# blink1mk3_micro1d2.net
KiCad netlist of a schematic drawn in EAGLE
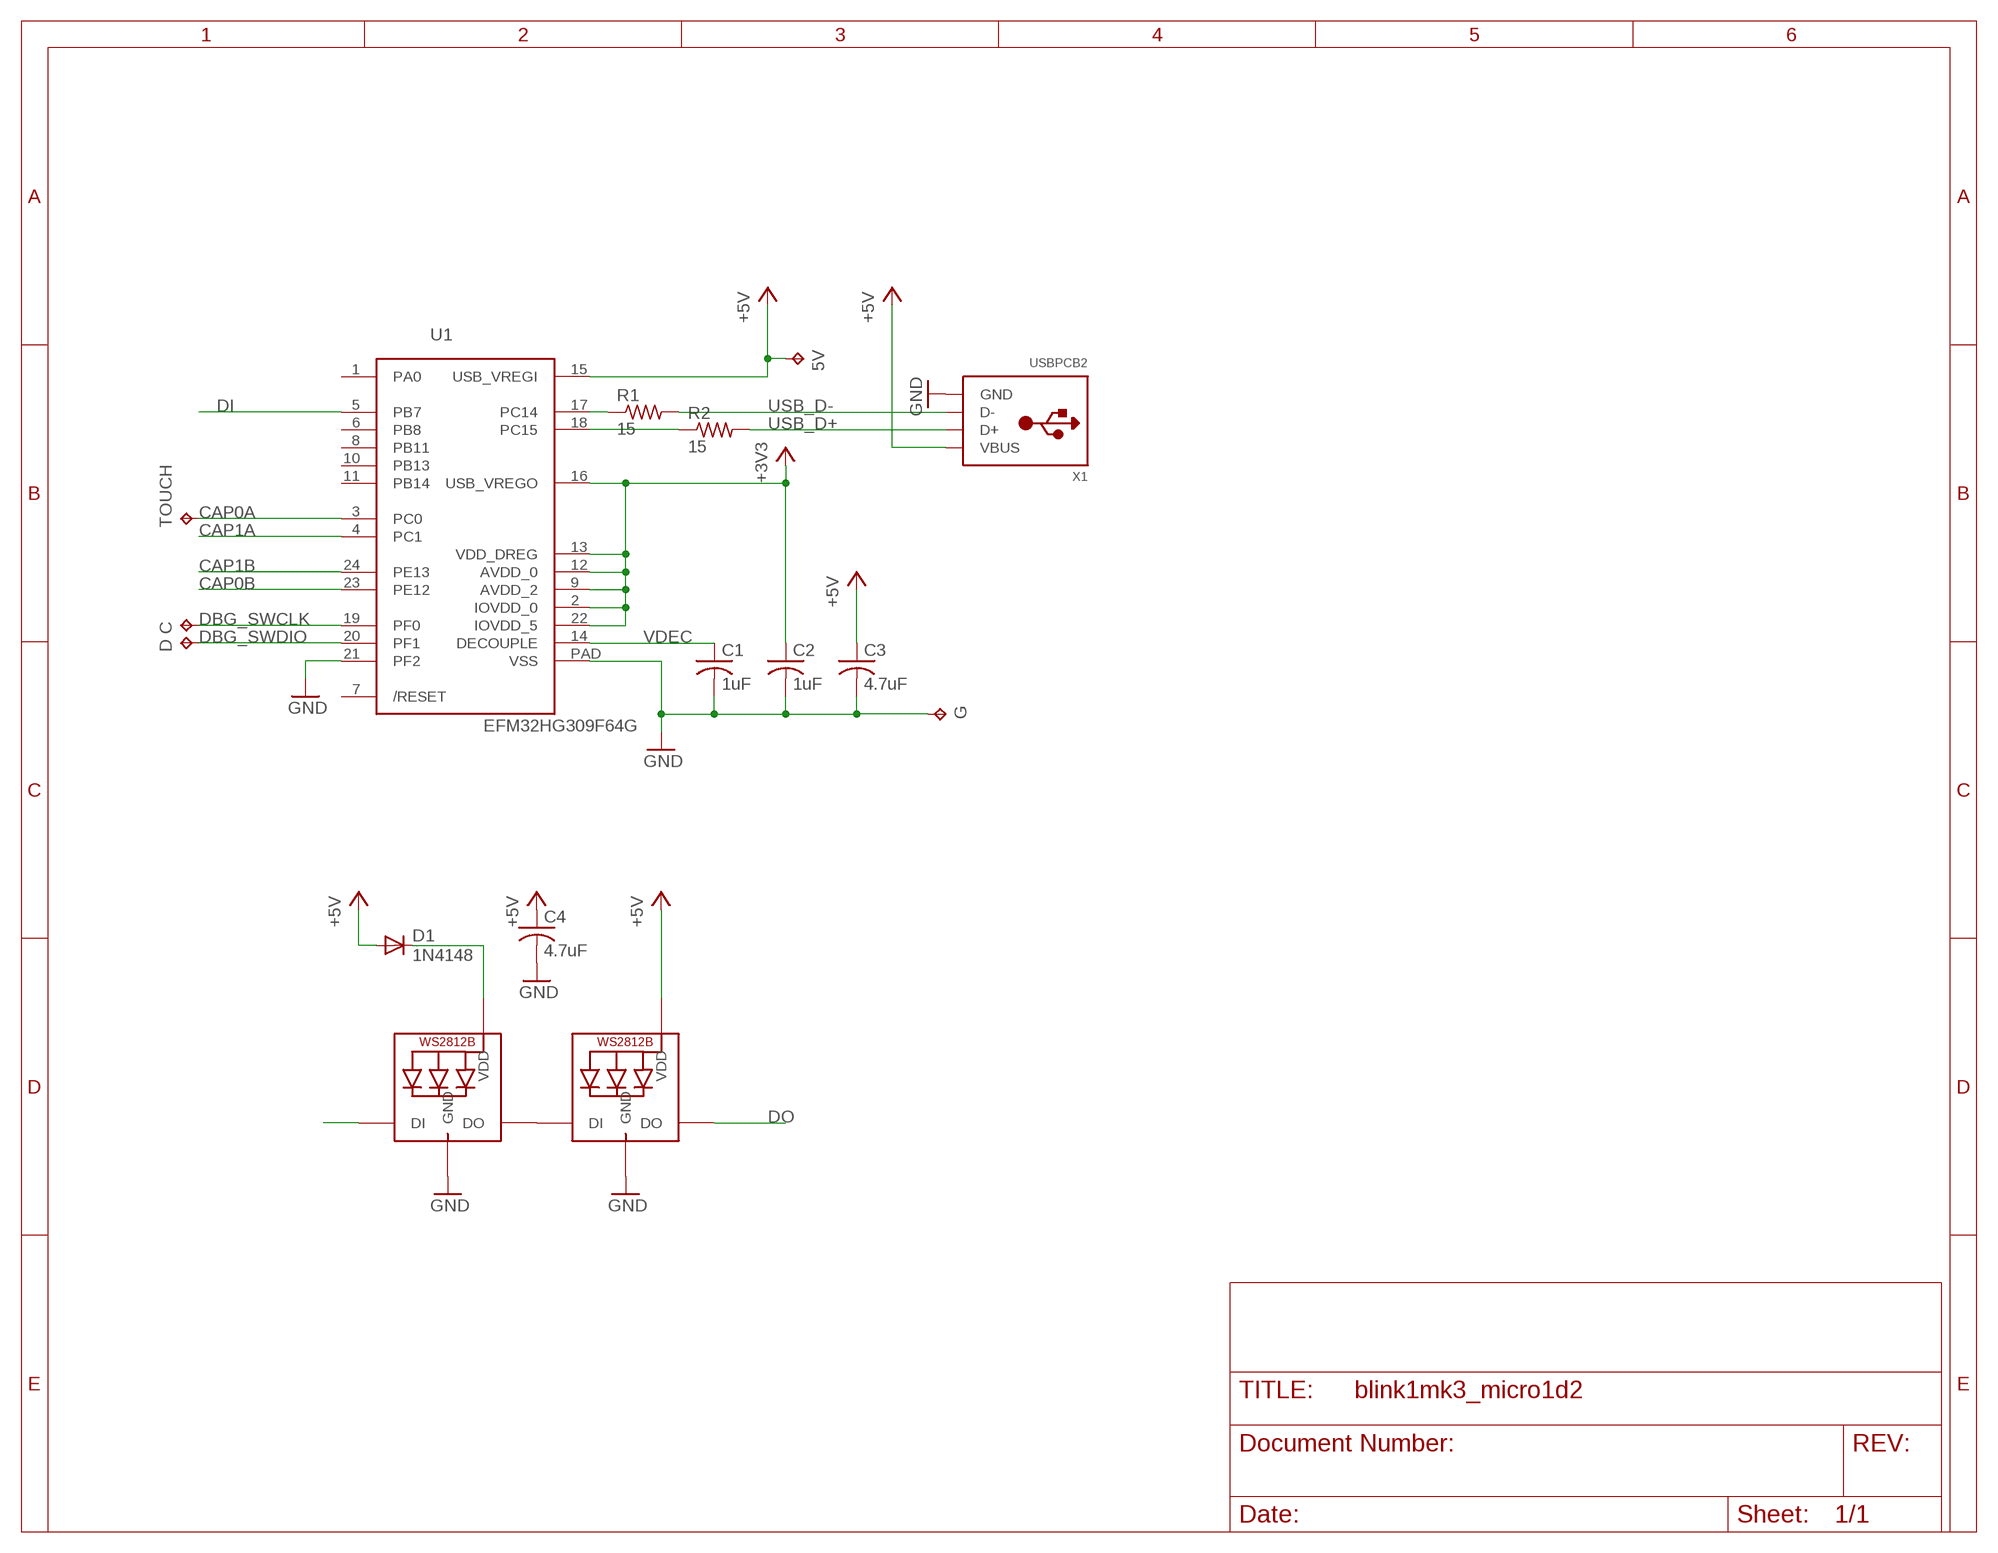
[diagram p0: schematic, sheet 1]

(export (version "E")
  (design (tool "Eeschema 10.0.6"))
  (components
    (comp (ref "5V")
      (value "TPTP10R")
      (footprint "eagle-import:TP10R")
      (libsource (lib "eagle-import") (part "TPTP10R"))
    )
    (comp (ref "C")
      (value "TPTP10R")
      (footprint "eagle-import:TP10R")
      (libsource (lib "eagle-import") (part "TPTP10R"))
    )
    (comp (ref "C1")
      (value "1uF")
      (footprint "eagle-import:C0402")
      (libsource (lib "eagle-import") (part "C-USC0402"))
    )
    (comp (ref "C2")
      (value "1uF")
      (footprint "eagle-import:C0402")
      (libsource (lib "eagle-import") (part "C-USC0402"))
    )
    (comp (ref "C3")
      (value "4.7uF")
      (footprint "eagle-import:C0402")
      (libsource (lib "eagle-import") (part "C-USC0402"))
    )
    (comp (ref "C4")
      (value "4.7uF")
      (footprint "eagle-import:C0402")
      (libsource (lib "eagle-import") (part "C-USC0402"))
    )
    (comp (ref "D")
      (value "TPTP10R")
      (footprint "eagle-import:TP10R")
      (libsource (lib "eagle-import") (part "TPTP10R"))
    )
    (comp (ref "D1")
      (value "1N4148")
      (footprint "eagle-import:SOD523")
      (libsource (lib "eagle-import") (part "DIODE-SOD523"))
    )
    (comp (ref "G")
      (value "TPTP10SQ")
      (footprint "eagle-import:TP10SQ")
      (libsource (lib "eagle-import") (part "TPTP10SQ"))
    )
    (comp (ref "LED1")
      (value "WS2812B4020SIDE")
      (footprint "eagle-import:SK6812-SIDE")
      (libsource (lib "eagle-import") (part "WS2812B4020SIDE"))
    )
    (comp (ref "LED2")
      (value "WS2812B4020SIDE")
      (footprint "eagle-import:SK6812-SIDE")
      (libsource (lib "eagle-import") (part "WS2812B4020SIDE"))
    )
    (comp (ref "R1")
      (value "15")
      (footprint "eagle-import:R0402")
      (libsource (lib "eagle-import") (part "R-US_R0402"))
    )
    (comp (ref "R2")
      (value "15")
      (footprint "eagle-import:R0402")
      (libsource (lib "eagle-import") (part "R-US_R0402"))
    )
    (comp (ref "TOUCH")
      (value "TPTP10R")
      (footprint "eagle-import:TP10R")
      (libsource (lib "eagle-import") (part "TPTP10R"))
    )
    (comp (ref "U1")
      (value "EFM32HG309F64G")
      (footprint "eagle-import:QFN24PAD")
      (libsource (lib "eagle-import") (part "EFM32HG309F64G"))
    )
    (comp (ref "X1")
      (value "USBPCB2")
      (footprint "eagle-import:USB-A-PCB-2")
      (libsource (lib "eagle-import") (part "USBPCB2"))
    )
  )
  (nets
    (net (code "1") (name "+3V3") (class "Default")
      (node (ref "C2") (pin "1") (pinfunction "1_1") (pintype "passive"))
      (node (ref "U1") (pin "12") (pinfunction "AVDD_0_12") (pintype "bidirectional"))
      (node (ref "U1") (pin "13") (pinfunction "VDD_DREG_13") (pintype "bidirectional"))
      (node (ref "U1") (pin "16") (pinfunction "USB_VREGO_16") (pintype "bidirectional"))
      (node (ref "U1") (pin "2") (pinfunction "IOVDD_0_2") (pintype "bidirectional"))
      (node (ref "U1") (pin "22") (pinfunction "IOVDD_5_22") (pintype "bidirectional"))
      (node (ref "U1") (pin "9") (pinfunction "AVDD_2_9") (pintype "bidirectional"))
    )
    (net (code "2") (name "+5V") (class "Default")
      (node (ref "5V") (pin "TP") (pinfunction "TP_TP") (pintype "input"))
      (node (ref "C3") (pin "1") (pinfunction "1_1") (pintype "passive"))
      (node (ref "C4") (pin "1") (pinfunction "1_1") (pintype "passive"))
      (node (ref "D1") (pin "A") (pinfunction "A_A") (pintype "passive"))
      (node (ref "LED2") (pin "1-VDD") (pinfunction "VDD_1-VDD") (pintype "power_in"))
      (node (ref "U1") (pin "15") (pinfunction "USB_VREGI_15") (pintype "bidirectional"))
      (node (ref "X1") (pin "5V") (pinfunction "VBUS_5V") (pintype "power_in"))
    )
    (net (code "3") (name "/CAP0A") (class "Default")
      (node (ref "TOUCH") (pin "TP") (pinfunction "TP_TP") (pintype "input"))
      (node (ref "U1") (pin "3") (pinfunction "PC0_3") (pintype "bidirectional"))
    )
    (net (code "4") (name "/CAP0B") (class "Default")
      (node (ref "U1") (pin "23") (pinfunction "PE12_23") (pintype "bidirectional"))
    )
    (net (code "5") (name "/CAP1A") (class "Default")
      (node (ref "U1") (pin "4") (pinfunction "PC1_4") (pintype "bidirectional"))
    )
    (net (code "6") (name "/CAP1B") (class "Default")
      (node (ref "U1") (pin "24") (pinfunction "PE13_24") (pintype "bidirectional"))
    )
    (net (code "7") (name "/DBG_SWCLK") (class "Default")
      (node (ref "C") (pin "TP") (pinfunction "TP_TP") (pintype "input"))
      (node (ref "U1") (pin "19") (pinfunction "PF0_19") (pintype "bidirectional"))
    )
    (net (code "8") (name "/DBG_SWDIO") (class "Default")
      (node (ref "D") (pin "TP") (pinfunction "TP_TP") (pintype "input"))
      (node (ref "U1") (pin "20") (pinfunction "PF1_20") (pintype "bidirectional"))
    )
    (net (code "9") (name "/DI") (class "Default")
      (node (ref "LED1") (pin "4-DIN") (pinfunction "DI_4-DIN") (pintype "input"))
      (node (ref "U1") (pin "5") (pinfunction "PB7_5") (pintype "bidirectional"))
    )
    (net (code "10") (name "/DO") (class "Default")
      (node (ref "LED2") (pin "2-DOUT") (pinfunction "DO_2-DOUT") (pintype "output"))
    )
    (net (code "11") (name "/USB_D+") (class "Default")
      (node (ref "R2") (pin "2") (pinfunction "2_2") (pintype "passive"))
      (node (ref "X1") (pin "USB_P") (pinfunction "D+_USB_P") (pintype "bidirectional"))
    )
    (net (code "12") (name "/USB_D-") (class "Default")
      (node (ref "R1") (pin "2") (pinfunction "2_2") (pintype "passive"))
      (node (ref "X1") (pin "USB_M") (pinfunction "D-_USB_M") (pintype "bidirectional"))
    )
    (net (code "13") (name "/VDEC") (class "Default")
      (node (ref "C1") (pin "1") (pinfunction "1_1") (pintype "passive"))
      (node (ref "U1") (pin "14") (pinfunction "DECOUPLE_14") (pintype "bidirectional"))
    )
    (net (code "14") (name "GND") (class "Default")
      (node (ref "C1") (pin "2") (pinfunction "2_2") (pintype "passive"))
      (node (ref "C2") (pin "2") (pinfunction "2_2") (pintype "passive"))
      (node (ref "C3") (pin "2") (pinfunction "2_2") (pintype "passive"))
      (node (ref "C4") (pin "2") (pinfunction "2_2") (pintype "passive"))
      (node (ref "G") (pin "TP") (pinfunction "TP_TP") (pintype "input"))
      (node (ref "LED1") (pin "3-GND") (pinfunction "GND_3-GND") (pintype "power_in"))
      (node (ref "LED2") (pin "3-GND") (pinfunction "GND_3-GND") (pintype "power_in"))
      (node (ref "U1") (pin "21") (pinfunction "PF2_21") (pintype "bidirectional"))
      (node (ref "U1") (pin "PAD") (pinfunction "VSS_PAD") (pintype "bidirectional"))
      (node (ref "X1") (pin "GND") (pinfunction "GND_GND") (pintype "power_in"))
    )
    (net (code "15") (name "Net-(LED1-DO)") (class "Default")
      (node (ref "LED1") (pin "2-DOUT") (pinfunction "DO_2-DOUT") (pintype "output"))
      (node (ref "LED2") (pin "4-DIN") (pinfunction "DI_4-DIN") (pintype "input"))
    )
    (net (code "16") (name "Net-(LED1-VDD)") (class "Default")
      (node (ref "D1") (pin "C") (pinfunction "C_C") (pintype "passive"))
      (node (ref "LED1") (pin "1-VDD") (pinfunction "VDD_1-VDD") (pintype "power_in"))
    )
    (net (code "17") (name "Net-(U1-PC14)") (class "Default")
      (node (ref "R1") (pin "1") (pinfunction "1_1") (pintype "passive"))
      (node (ref "U1") (pin "17") (pinfunction "PC14_17") (pintype "bidirectional"))
    )
    (net (code "18") (name "Net-(U1-PC15)") (class "Default")
      (node (ref "R2") (pin "1") (pinfunction "1_1") (pintype "passive"))
      (node (ref "U1") (pin "18") (pinfunction "PC15_18") (pintype "bidirectional"))
    )
    (net (code "19") (name "unconnected-(U1-PA0-Pad1)") (class "Default")
      (node (ref "U1") (pin "1") (pinfunction "PA0_1") (pintype "bidirectional"))
    )
    (net (code "20") (name "unconnected-(U1-PB8-Pad6)") (class "Default")
      (node (ref "U1") (pin "6") (pinfunction "PB8_6") (pintype "bidirectional"))
    )
    (net (code "21") (name "unconnected-(U1-PB11-Pad8)") (class "Default")
      (node (ref "U1") (pin "8") (pinfunction "PB11_8") (pintype "bidirectional"))
    )
    (net (code "22") (name "unconnected-(U1-PB13-Pad10)") (class "Default")
      (node (ref "U1") (pin "10") (pinfunction "PB13_10") (pintype "bidirectional"))
    )
    (net (code "23") (name "unconnected-(U1-PB14-Pad11)") (class "Default")
      (node (ref "U1") (pin "11") (pinfunction "PB14_11") (pintype "bidirectional"))
    )
    (net (code "24") (name "unconnected-(U1-{slash}RESET-Pad7)") (class "Default")
      (node (ref "U1") (pin "7") (pinfunction "/RESET_7") (pintype "bidirectional"))
    )
  )
)
